# TMTGP_Sensors.net
KiCad netlist of a schematic drawn in Altium Designer
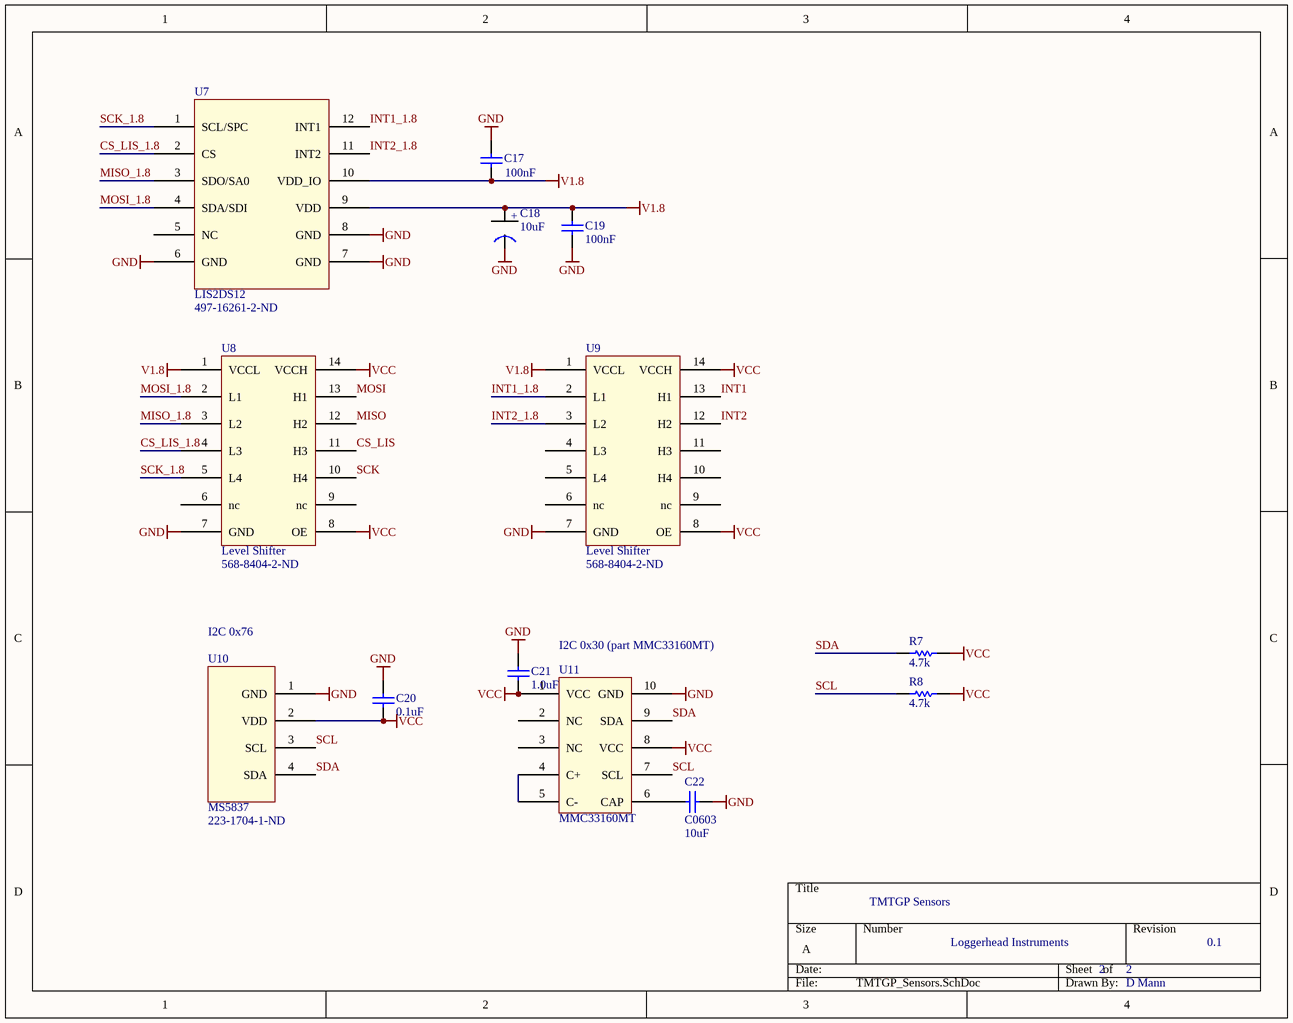
[diagram p0: TMTGP_Sensors.SchDoc]

(export (version "E")
  (design (tool "Eeschema 10.0.6"))
  (components
    (comp (ref "C17")
      (value "100nF")
      (footprint "0402")
      (description "Ceramic Chip Capacitor - Standard")
      (fields (field (name "PUBLISHER") "Altium Limited"))
      (libsource (lib "KEMET Chip Capacitor") (part "C0402"))
    )
    (comp (ref "C18") (value "10uF") (footprint "Tant0805") (libsource (lib "Loggerhead") (part "Tant0805")))
    (comp (ref "C19")
      (value "100nF")
      (footprint "0402")
      (description "Ceramic Chip Capacitor - Standard")
      (fields (field (name "PUBLISHER") "Altium Limited"))
      (libsource (lib "KEMET Chip Capacitor") (part "C0402"))
    )
    (comp (ref "C20")
      (value "0.1uF")
      (footprint "0402")
      (description "Ceramic Chip Capacitor - Standard")
      (fields (field (name "PUBLISHER") "Altium Limited"))
      (libsource (lib "KEMET Chip Capacitor") (part "C0402"))
    )
    (comp (ref "C21")
      (value "1.0uF")
      (footprint "0402")
      (description "Ceramic Chip Capacitor - Standard")
      (fields (field (name "PUBLISHER") "Altium Limited"))
      (libsource (lib "KEMET Chip Capacitor") (part "C0402"))
    )
    (comp (ref "C22")
      (value "C0603")
      (footprint "0603")
      (description "Ceramic Chip Capacitor - Standard")
      (fields (field (name "ALTIUM_VALUE") "10uF") (field (name "PUBLISHER") "Altium Limited"))
      (libsource (lib "KEMET Chip Capacitor") (part "C0603"))
    )
    (comp (ref "R7")
      (value "4.7k")
      (footprint "3-0603")
      (fields (field (name "PUBLISHER") "Altium Limited"))
      (libsource (lib "Panasonic Resistor") (part "ERJ3RK"))
    )
    (comp (ref "R8")
      (value "4.7k")
      (footprint "3-0603")
      (fields (field (name "PUBLISHER") "Altium Limited"))
      (libsource (lib "Panasonic Resistor") (part "ERJ3RK"))
    )
    (comp (ref "U7")
      (value "LIS2DS12")
      (footprint "LGA-12")
      (fields (field (name "SUPPLIER PART NUMBER 1") "497-16261-2-ND"))
      (libsource (lib "Loggerhead") (part "LIS2DS12"))
    )
    (comp (ref "U8")
      (value "Level Shifter")
      (footprint "DHVQFN14")
      (description "Voltage level translator")
      (fields (field (name "SUPPLIER PART NUMBER 1") "568-8404-2-ND"))
      (libsource (lib "Loggerhead") (part "NTB0104"))
    )
    (comp (ref "U9")
      (value "Level Shifter")
      (footprint "DHVQFN14")
      (description "Voltage level translator")
      (fields (field (name "SUPPLIER PART NUMBER 1") "568-8404-2-ND"))
      (libsource (lib "Loggerhead") (part "NTB0104"))
    )
    (comp (ref "U10")
      (value "MS5837")
      (footprint "MS5837")
      (description "Pressure/Temp")
      (fields (field (name "SUPPLIER PART NUMBER 1") "223-1704-1-ND"))
      (libsource (lib "Loggerhead") (part "MS5837"))
    )
    (comp (ref "U11")
      (value "MMC33160MT")
      (footprint "MMC33160MT")
      (libsource (lib "Loggerhead") (part "MMC33160MT"))
    )
  )
  (nets
    (net (code "1") (name "/CS_LIS") (class "Default")
      (node (ref "U8") (pin "11") (pinfunction "H3_11") (pintype "passive"))
    )
    (net (code "2") (name "/CS_LIS_1.8") (class "Default")
      (node (ref "U7") (pin "2") (pinfunction "CS_2") (pintype "passive"))
      (node (ref "U8") (pin "4") (pinfunction "L3_4") (pintype "passive"))
    )
    (net (code "3") (name "/INT1") (class "Default")
      (node (ref "U9") (pin "13") (pinfunction "H1_13") (pintype "passive"))
    )
    (net (code "4") (name "/INT1_1.8") (class "Default")
      (node (ref "U7") (pin "12") (pinfunction "INT1_12") (pintype "passive"))
      (node (ref "U9") (pin "2") (pinfunction "L1_2") (pintype "passive"))
    )
    (net (code "5") (name "/INT2") (class "Default")
      (node (ref "U9") (pin "12") (pinfunction "H2_12") (pintype "passive"))
    )
    (net (code "6") (name "/INT2_1.8") (class "Default")
      (node (ref "U7") (pin "11") (pinfunction "INT2_11") (pintype "passive"))
      (node (ref "U9") (pin "3") (pinfunction "L2_3") (pintype "passive"))
    )
    (net (code "7") (name "/MISO") (class "Default")
      (node (ref "U8") (pin "12") (pinfunction "H2_12") (pintype "passive"))
    )
    (net (code "8") (name "/MISO_1.8") (class "Default")
      (node (ref "U7") (pin "3") (pinfunction "SDO/SA0_3") (pintype "passive"))
      (node (ref "U8") (pin "3") (pinfunction "L2_3") (pintype "passive"))
    )
    (net (code "9") (name "/MOSI") (class "Default")
      (node (ref "U8") (pin "13") (pinfunction "H1_13") (pintype "passive"))
    )
    (net (code "10") (name "/MOSI_1.8") (class "Default")
      (node (ref "U7") (pin "4") (pinfunction "SDA/SDI_4") (pintype "passive"))
      (node (ref "U8") (pin "2") (pinfunction "L1_2") (pintype "passive"))
    )
    (net (code "11") (name "/SCK") (class "Default")
      (node (ref "U8") (pin "10") (pinfunction "H4_10") (pintype "passive"))
    )
    (net (code "12") (name "/SCK_1.8") (class "Default")
      (node (ref "U7") (pin "1") (pinfunction "SCL/SPC_1") (pintype "passive"))
      (node (ref "U8") (pin "5") (pinfunction "L4_5") (pintype "passive"))
    )
    (net (code "13") (name "/SCL") (class "Default")
      (node (ref "R8") (pin "1") (pinfunction "1_1") (pintype "passive"))
      (node (ref "U10") (pin "3") (pinfunction "SCL_3") (pintype "passive"))
      (node (ref "U11") (pin "7") (pinfunction "SCL_7") (pintype "passive"))
    )
    (net (code "14") (name "/SDA") (class "Default")
      (node (ref "R7") (pin "2") (pinfunction "2_2") (pintype "passive"))
      (node (ref "U10") (pin "4") (pinfunction "SDA_4") (pintype "passive"))
      (node (ref "U11") (pin "9") (pinfunction "SDA_9") (pintype "passive"))
    )
    (net (code "15") (name "GND") (class "Default")
      (node (ref "C17") (pin "2") (pinfunction "2_2") (pintype "passive"))
      (node (ref "C18") (pin "1") (pinfunction "GND_1") (pintype "passive"))
      (node (ref "C19") (pin "2") (pinfunction "2_2") (pintype "passive"))
      (node (ref "C20") (pin "2") (pinfunction "2_2") (pintype "passive"))
      (node (ref "C21") (pin "2") (pinfunction "2_2") (pintype "passive"))
      (node (ref "C22") (pin "1") (pinfunction "1_1") (pintype "passive"))
      (node (ref "U10") (pin "1") (pinfunction "GND_1") (pintype "passive"))
      (node (ref "U11") (pin "10") (pinfunction "GND_10") (pintype "passive"))
      (node (ref "U7") (pin "6") (pinfunction "GND_6") (pintype "passive"))
      (node (ref "U7") (pin "7") (pinfunction "GND_7") (pintype "passive"))
      (node (ref "U7") (pin "8") (pinfunction "GND_8") (pintype "passive"))
      (node (ref "U8") (pin "7") (pinfunction "GND_7") (pintype "passive"))
      (node (ref "U9") (pin "7") (pinfunction "GND_7") (pintype "passive"))
    )
    (net (code "16") (name "Net-(U11-C+)") (class "Default")
      (node (ref "U11") (pin "4") (pinfunction "C+_4") (pintype "passive"))
      (node (ref "U11") (pin "5") (pinfunction "C-_5") (pintype "passive"))
    )
    (net (code "17") (name "Net-(U11-CAP)") (class "Default")
      (node (ref "C22") (pin "2") (pinfunction "2_2") (pintype "passive"))
      (node (ref "U11") (pin "6") (pinfunction "CAP_6") (pintype "passive"))
    )
    (net (code "18") (name "V1.8") (class "Default")
      (node (ref "C17") (pin "1") (pinfunction "1_1") (pintype "passive"))
      (node (ref "C18") (pin "2") (pinfunction "+_2") (pintype "passive"))
      (node (ref "C19") (pin "1") (pinfunction "1_1") (pintype "passive"))
      (node (ref "U7") (pin "10") (pinfunction "VDD_IO_10") (pintype "passive"))
      (node (ref "U7") (pin "9") (pinfunction "VDD_9") (pintype "passive"))
      (node (ref "U8") (pin "1") (pinfunction "VCCL_1") (pintype "passive"))
      (node (ref "U9") (pin "1") (pinfunction "VCCL_1") (pintype "passive"))
    )
    (net (code "19") (name "VCC") (class "Default")
      (node (ref "C20") (pin "1") (pinfunction "1_1") (pintype "passive"))
      (node (ref "C21") (pin "1") (pinfunction "1_1") (pintype "passive"))
      (node (ref "R7") (pin "1") (pinfunction "1_1") (pintype "passive"))
      (node (ref "R8") (pin "2") (pinfunction "2_2") (pintype "passive"))
      (node (ref "U10") (pin "2") (pinfunction "VDD_2") (pintype "passive"))
      (node (ref "U11") (pin "1") (pinfunction "VCC_1") (pintype "passive"))
      (node (ref "U11") (pin "8") (pinfunction "VCC_8") (pintype "passive"))
      (node (ref "U8") (pin "14") (pinfunction "VCCH_14") (pintype "passive"))
      (node (ref "U8") (pin "8") (pinfunction "OE_8") (pintype "passive"))
      (node (ref "U9") (pin "14") (pinfunction "VCCH_14") (pintype "passive"))
      (node (ref "U9") (pin "8") (pinfunction "OE_8") (pintype "passive"))
    )
    (net (code "20") (name "unconnected-(U7-NC-Pad5)") (class "Default")
      (node (ref "U7") (pin "5") (pinfunction "NC_5") (pintype "passive"))
    )
    (net (code "21") (name "unconnected-(U8-nc-Pad6)") (class "Default")
      (node (ref "U8") (pin "6") (pinfunction "nc_6") (pintype "passive"))
    )
    (net (code "22") (name "unconnected-(U8-nc-Pad9)") (class "Default")
      (node (ref "U8") (pin "9") (pinfunction "nc_9") (pintype "passive"))
    )
    (net (code "23") (name "unconnected-(U9-H3-Pad11)") (class "Default")
      (node (ref "U9") (pin "11") (pinfunction "H3_11") (pintype "passive"))
    )
    (net (code "24") (name "unconnected-(U9-H4-Pad10)") (class "Default")
      (node (ref "U9") (pin "10") (pinfunction "H4_10") (pintype "passive"))
    )
    (net (code "25") (name "unconnected-(U9-L3-Pad4)") (class "Default")
      (node (ref "U9") (pin "4") (pinfunction "L3_4") (pintype "passive"))
    )
    (net (code "26") (name "unconnected-(U9-L4-Pad5)") (class "Default")
      (node (ref "U9") (pin "5") (pinfunction "L4_5") (pintype "passive"))
    )
    (net (code "27") (name "unconnected-(U9-nc-Pad6)") (class "Default")
      (node (ref "U9") (pin "6") (pinfunction "nc_6") (pintype "passive"))
    )
    (net (code "28") (name "unconnected-(U9-nc-Pad9)") (class "Default")
      (node (ref "U9") (pin "9") (pinfunction "nc_9") (pintype "passive"))
    )
    (net (code "29") (name "unconnected-(U11-NC-Pad2)") (class "Default")
      (node (ref "U11") (pin "2") (pinfunction "NC_2") (pintype "passive"))
    )
    (net (code "30") (name "unconnected-(U11-NC-Pad3)") (class "Default")
      (node (ref "U11") (pin "3") (pinfunction "NC_3") (pintype "passive"))
    )
  )
)
